# EEPROM.net
KiCad netlist of a schematic drawn in Altium Designer
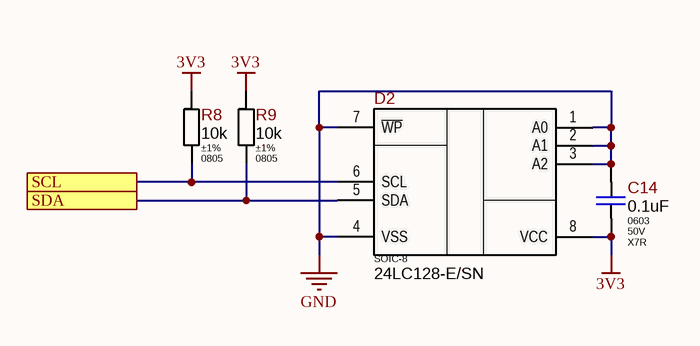
[diagram p0: EEPROM.SchDoc]

(export (version "E")
  (design (tool "Eeschema 10.0.6"))
  (components
    (comp (ref "C14")
      (value "0.1uF")
      (footprint "C_CERAMIC_0603_MED")
      (description "100nF 50V X7R ±10% 0603 Ceramic Capacitor RoHS")
      (fields
        (field (name "PACKAGE") "0603")
        (field (name "VOLTAGE") "50V")
        (field (name "DIELECTRIC TYPE") "X7R")
        (field (name "PART NUMBER") "CL10B104KB8NNND")
        (field (name "MANUFACTURER") "Samsung Electro-Mechanics")
      )
      (libsource (lib "capacitors") (part "CL10B104KB8NNND"))
    )
    (comp (ref "D2")
      (value "24LC128-E/SN")
      (footprint "SOIC-8_W3.9MM")
      (description "EEPROM Memory IC 128Kb (16K x 8), I2C, 400kHz, 900ns, SOIC-8")
      (fields
        (field (name "MANUFACTURER") "Microchip Technology")
        (field (name "PACKAGE") "SOIC-8")
        (field (name "PART NUMBER") "24LC128-E/SN")
      )
      (libsource (lib "ic") (part "24LC128-E/SN"))
    )
    (comp (ref "R8")
      (value "10k")
      (footprint "R_ANY_CHIP_0805_MED")
      (description "10 kOhms ±1%, 1/8W 0805 Thick Film Resistor")
      (fields
        (field (name "TOLERANCE") "±1%")
        (field (name "PACKAGE") "0805")
        (field (name "PART NUMBER") "RC0805FR-0710K2L")
        (field (name "MANUFACTURER") "Yageo")
      )
      (libsource (lib "resistors") (part "RC0805FR-0710K2L"))
    )
    (comp (ref "R9")
      (value "10k")
      (footprint "R_ANY_CHIP_0805_MED")
      (description "10 kOhms ±1%, 1/8W 0805 Thick Film Resistor")
      (fields
        (field (name "TOLERANCE") "±1%")
        (field (name "PACKAGE") "0805")
        (field (name "PART NUMBER") "RC0805FR-0710K2L")
        (field (name "MANUFACTURER") "Yageo")
      )
      (libsource (lib "resistors") (part "RC0805FR-0710K2L"))
    )
  )
  (nets
    (net (code "1") (name "/SCL") (class "Default")
      (node (ref "D2") (pin "6") (pinfunction "SCL_6") (pintype "passive"))
      (node (ref "R8") (pin "1") (pintype "passive"))
    )
    (net (code "2") (name "/SDA") (class "Default")
      (node (ref "D2") (pin "5") (pinfunction "SDA_5") (pintype "passive"))
      (node (ref "R9") (pin "1") (pintype "passive"))
    )
    (net (code "3") (name "3V3") (class "Default")
      (node (ref "C14") (pin "1") (pinfunction "1_1") (pintype "passive"))
      (node (ref "D2") (pin "8") (pinfunction "VCC_8") (pintype "passive"))
      (node (ref "R8") (pin "2") (pintype "passive"))
      (node (ref "R9") (pin "2") (pintype "passive"))
    )
    (net (code "4") (name "GND") (class "Default")
      (node (ref "C14") (pin "2") (pinfunction "2_2") (pintype "passive"))
      (node (ref "D2") (pin "1") (pinfunction "A0_1") (pintype "passive"))
      (node (ref "D2") (pin "2") (pinfunction "A1_2") (pintype "passive"))
      (node (ref "D2") (pin "3") (pinfunction "A2_3") (pintype "passive"))
      (node (ref "D2") (pin "4") (pinfunction "VSS_4") (pintype "passive"))
      (node (ref "D2") (pin "7") (pinfunction "~{WP}_7") (pintype "passive"))
    )
  )
)
